# ETH.net
KiCad netlist of a schematic drawn in Altium Designer
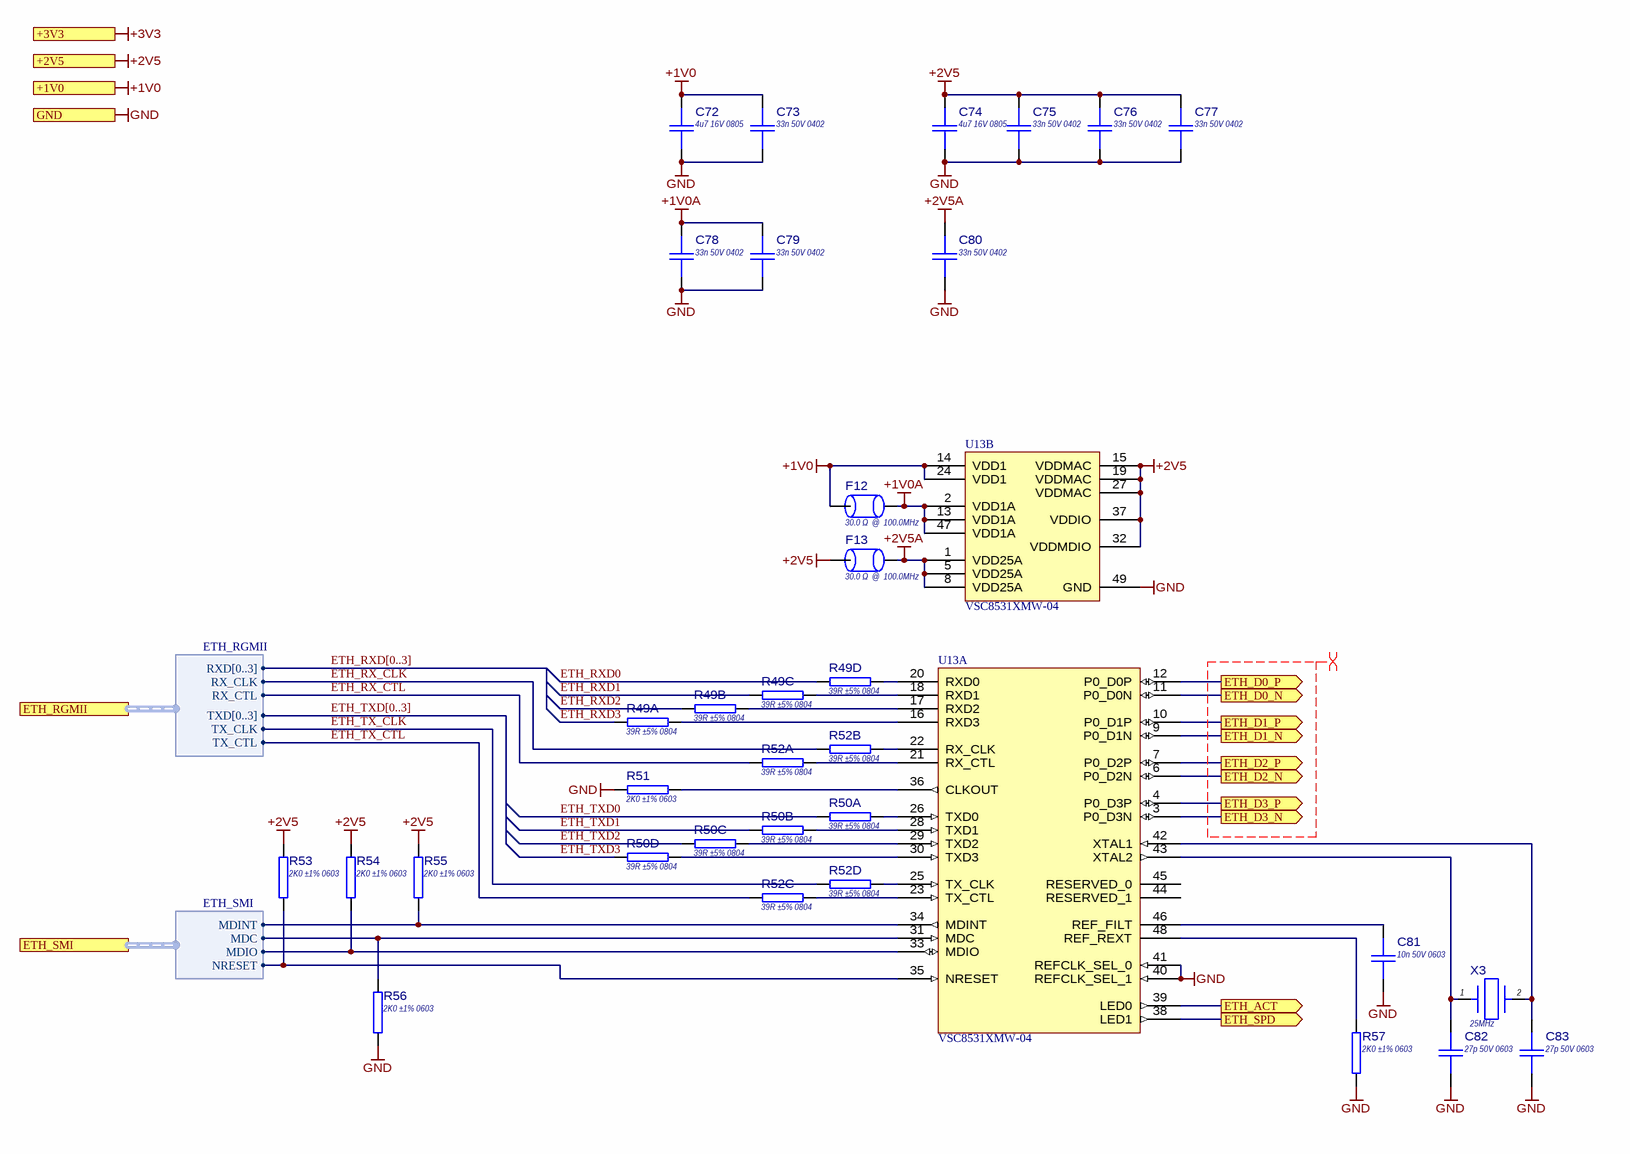
[diagram p0: ETH.SchDoc]

(export (version "E")
  (design (tool "Eeschema 10.0.6"))
  (components
    (comp (ref "C72")
      (value "4u7 16V 0805")
      (footprint "CAPC2012X140N")
      (description "4u7 16V X7R ±10% 0805 (2012 metric)")
      (fields (field (name "PARTNUMBER") "GRM21BR71C475KA73") (field (name "TOLERANCE") "10%"))
      (libsource (lib "Omnisys Vault") (part "CAP-2PIN"))
    )
    (comp (ref "C73")
      (value "33n 50V 0402")
      (footprint "CAPC1005X55N")
      (description "33n 50V X7R ±10% 0402 (1005 metric)")
      (fields (field (name "PARTNUMBER") "GRM155R71H333KE14") (field (name "TOLERANCE") "10%"))
      (libsource (lib "Omnisys Vault") (part "CAP-2PIN"))
    )
    (comp (ref "C74")
      (value "4u7 16V 0805")
      (footprint "CAPC2012X140N")
      (description "4u7 16V X7R ±10% 0805 (2012 metric)")
      (fields (field (name "PARTNUMBER") "GRM21BR71C475KA73") (field (name "TOLERANCE") "10%"))
      (libsource (lib "Omnisys Vault") (part "CAP-2PIN"))
    )
    (comp (ref "C75")
      (value "33n 50V 0402")
      (footprint "CAPC1005X55N")
      (description "33n 50V X7R ±10% 0402 (1005 metric)")
      (fields (field (name "PARTNUMBER") "GRM155R71H333KE14") (field (name "TOLERANCE") "10%"))
      (libsource (lib "Omnisys Vault") (part "CAP-2PIN"))
    )
    (comp (ref "C76")
      (value "33n 50V 0402")
      (footprint "CAPC1005X55N")
      (description "33n 50V X7R ±10% 0402 (1005 metric)")
      (fields (field (name "PARTNUMBER") "GRM155R71H333KE14") (field (name "TOLERANCE") "10%"))
      (libsource (lib "Omnisys Vault") (part "CAP-2PIN"))
    )
    (comp (ref "C77")
      (value "33n 50V 0402")
      (footprint "CAPC1005X55N")
      (description "33n 50V X7R ±10% 0402 (1005 metric)")
      (fields (field (name "PARTNUMBER") "GRM155R71H333KE14") (field (name "TOLERANCE") "10%"))
      (libsource (lib "Omnisys Vault") (part "CAP-2PIN"))
    )
    (comp (ref "C78")
      (value "33n 50V 0402")
      (footprint "CAPC1005X55N")
      (description "33n 50V X7R ±10% 0402 (1005 metric)")
      (fields (field (name "PARTNUMBER") "GRM155R71H333KE14") (field (name "TOLERANCE") "10%"))
      (libsource (lib "Omnisys Vault") (part "CAP-2PIN"))
    )
    (comp (ref "C79")
      (value "33n 50V 0402")
      (footprint "CAPC1005X55N")
      (description "33n 50V X7R ±10% 0402 (1005 metric)")
      (fields (field (name "PARTNUMBER") "GRM155R71H333KE14") (field (name "TOLERANCE") "10%"))
      (libsource (lib "Omnisys Vault") (part "CAP-2PIN"))
    )
    (comp (ref "C80")
      (value "33n 50V 0402")
      (footprint "CAPC1005X55N")
      (description "33n 50V X7R ±10% 0402 (1005 metric)")
      (fields (field (name "PARTNUMBER") "GRM155R71H333KE14") (field (name "TOLERANCE") "10%"))
      (libsource (lib "Omnisys Vault") (part "CAP-2PIN"))
    )
    (comp (ref "C81")
      (value "10n 50V 0603")
      (footprint "CAPC1608X90N")
      (description "10n 50V C0G ±5% 0603 (1608 metric)")
      (fields (field (name "PARTNUMBER") "GRM1885C1H103JA01") (field (name "TOLERANCE") "±5%"))
      (libsource (lib "Omnisys Vault") (part "CAP-2PIN"))
    )
    (comp (ref "C82")
      (value "27p 50V 0603")
      (footprint "CAPC1608X90N")
      (description "27p 50V C0G ±5% 0603 (1608 metric)")
      (fields (field (name "PARTNUMBER") "GRM1885C1H270JA01") (field (name "TOLERANCE") "±5%"))
      (libsource (lib "Omnisys Vault") (part "CAP-2PIN"))
    )
    (comp (ref "C83")
      (value "27p 50V 0603")
      (footprint "CAPC1608X90N")
      (description "27p 50V C0G ±5% 0603 (1608 metric)")
      (fields (field (name "PARTNUMBER") "GRM1885C1H270JA01") (field (name "TOLERANCE") "±5%"))
      (libsource (lib "Omnisys Vault") (part "CAP-2PIN"))
    )
    (comp (ref "F12")
      (value "30.0 Ω  @  100.0MHz")
      (footprint "INDC2012X11L")
      (description "Ferrite bead, Würth Elektronik WE-CBF 2012 (0805), 74279206 ,  30.0 Ω  @  100.0MHz")
      (fields (field (name "PARTNUMBER") "74279206"))
      (libsource (lib "Omnisys Vault") (part "BEAD-2PIN"))
    )
    (comp (ref "F13")
      (value "30.0 Ω  @  100.0MHz")
      (footprint "INDC2012X11L")
      (description "Ferrite bead, Würth Elektronik WE-CBF 2012 (0805), 74279206 ,  30.0 Ω  @  100.0MHz")
      (fields (field (name "PARTNUMBER") "74279206"))
      (libsource (lib "Omnisys Vault") (part "BEAD-2PIN"))
    )
    (comp (ref "R49")
      (value "39R ±5% 0804")
      (footprint "RESCAXS50P100X200X45-8N")
      (description "39R ±5% ±200 ppm/˚C 0.031W 50V 0804 (2010 metric)")
      (fields (field (name "TOLERANCE") "±5%") (field (name "PARTNUMBER") "EXB-28V390J"))
      (libsource (lib "Omnisys Vault") (part "RES_ARRAY-8PIN"))
    )
    (comp (ref "R50")
      (value "39R ±5% 0804")
      (footprint "RESCAXS50P100X200X45-8N")
      (description "39R ±5% ±200 ppm/˚C 0.031W 50V 0804 (2010 metric)")
      (fields (field (name "TOLERANCE") "±5%") (field (name "PARTNUMBER") "EXB-28V390J"))
      (libsource (lib "Omnisys Vault") (part "RES_ARRAY-8PIN"))
    )
    (comp (ref "R51")
      (value "2K0 ±1% 0603")
      (footprint "RESC1608N")
      (description "2K0 ±1% ±100 ppm/˚C 0.10W 75V 0603 (1608 metric)")
      (fields (field (name "POWER") "100mW") (field (name "TOLERANCE") "1%"))
      (libsource (lib "Omnisys Vault") (part "RES-2PIN"))
    )
    (comp (ref "R52")
      (value "39R ±5% 0804")
      (footprint "RESCAXS50P100X200X45-8N")
      (description "39R ±5% ±200 ppm/˚C 0.031W 50V 0804 (2010 metric)")
      (fields (field (name "TOLERANCE") "±5%") (field (name "PARTNUMBER") "EXB-28V390J"))
      (libsource (lib "Omnisys Vault") (part "RES_ARRAY-8PIN"))
    )
    (comp (ref "R53")
      (value "2K0 ±1% 0603")
      (footprint "RESC1608N")
      (description "2K0 ±1% ±100 ppm/˚C 0.10W 75V 0603 (1608 metric)")
      (fields (field (name "POWER") "100mW") (field (name "TOLERANCE") "1%"))
      (libsource (lib "Omnisys Vault") (part "RES-2PIN"))
    )
    (comp (ref "R54")
      (value "2K0 ±1% 0603")
      (footprint "RESC1608N")
      (description "2K0 ±1% ±100 ppm/˚C 0.10W 75V 0603 (1608 metric)")
      (fields (field (name "POWER") "100mW") (field (name "TOLERANCE") "1%"))
      (libsource (lib "Omnisys Vault") (part "RES-2PIN"))
    )
    (comp (ref "R55")
      (value "2K0 ±1% 0603")
      (footprint "RESC1608N")
      (description "2K0 ±1% ±100 ppm/˚C 0.10W 75V 0603 (1608 metric)")
      (fields (field (name "POWER") "100mW") (field (name "TOLERANCE") "1%"))
      (libsource (lib "Omnisys Vault") (part "RES-2PIN"))
    )
    (comp (ref "R56")
      (value "2K0 ±1% 0603")
      (footprint "RESC1608N")
      (description "2K0 ±1% ±100 ppm/˚C 0.10W 75V 0603 (1608 metric)")
      (fields (field (name "POWER") "100mW") (field (name "TOLERANCE") "1%"))
      (libsource (lib "Omnisys Vault") (part "RES-2PIN"))
    )
    (comp (ref "R57")
      (value "2K0 ±1% 0603")
      (footprint "RESC1608N")
      (description "2K0 ±1% ±100 ppm/˚C 0.10W 75V 0603 (1608 metric)")
      (fields (field (name "POWER") "100mW") (field (name "TOLERANCE") "1%"))
      (libsource (lib "Omnisys Vault") (part "RES-2PIN"))
    )
    (comp (ref "U13")
      (value "VSC8531XMW-04")
      (footprint "QFN40P600X600X90_HS-49N")
      (description "Single Port Gigabit Ethernet Copper PHY")
      (libsource (lib "Omnisys Vault") (part "VSC8531XMW-04"))
    )
    (comp (ref "X3")
      (value "25MHz")
      (footprint "XTAL_5x3.2MM")
      (description "25MHz 5 x 3.2 mm SMD GLASS CRYSTAL, 7A-25.000MAAJ-T")
      (fields (field (name "PARTNUMBER") "7A-25.000MAAJ-T"))
      (libsource (lib "Omnisys Vault") (part "XTAL-2PIN"))
    )
  )
  (nets
    (net (code "3") (name "+1V0") (class "Default")
      (node (ref "C72") (pin "2") (pinfunction "2_2") (pintype "passive"))
      (node (ref "C73") (pin "1") (pinfunction "1_1") (pintype "passive"))
      (node (ref "F12") (pin "1") (pinfunction "1_1") (pintype "passive"))
      (node (ref "U13") (pin "14") (pinfunction "VDD1_14") (pintype "power_in"))
      (node (ref "U13") (pin "24") (pinfunction "VDD1_24") (pintype "power_in"))
    )
    (net (code "4") (name "+1V0A") (class "Default")
      (node (ref "C78") (pin "1") (pinfunction "1_1") (pintype "passive"))
      (node (ref "C79") (pin "1") (pinfunction "1_1") (pintype "passive"))
      (node (ref "F12") (pin "2") (pinfunction "2_2") (pintype "passive"))
      (node (ref "U13") (pin "13") (pinfunction "VDD1A_13") (pintype "power_in"))
      (node (ref "U13") (pin "2") (pinfunction "VDD1A_2") (pintype "power_in"))
      (node (ref "U13") (pin "47") (pinfunction "VDD1A_47") (pintype "power_in"))
    )
    (net (code "5") (name "+2V5") (class "Default")
      (node (ref "C74") (pin "2") (pinfunction "2_2") (pintype "passive"))
      (node (ref "C75") (pin "1") (pinfunction "1_1") (pintype "passive"))
      (node (ref "C76") (pin "1") (pinfunction "1_1") (pintype "passive"))
      (node (ref "C77") (pin "1") (pinfunction "1_1") (pintype "passive"))
      (node (ref "F13") (pin "1") (pinfunction "1_1") (pintype "passive"))
      (node (ref "R53") (pin "2") (pinfunction "2_2") (pintype "passive"))
      (node (ref "R54") (pin "2") (pinfunction "2_2") (pintype "passive"))
      (node (ref "R55") (pin "2") (pinfunction "2_2") (pintype "passive"))
      (node (ref "U13") (pin "15") (pinfunction "VDDMAC_15") (pintype "power_in"))
      (node (ref "U13") (pin "19") (pinfunction "VDDMAC_19") (pintype "power_in"))
      (node (ref "U13") (pin "27") (pinfunction "VDDMAC_27") (pintype "power_in"))
      (node (ref "U13") (pin "32") (pinfunction "VDDMDIO_32") (pintype "power_in"))
      (node (ref "U13") (pin "37") (pinfunction "VDDIO_37") (pintype "power_in"))
    )
    (net (code "6") (name "+2V5A") (class "Default")
      (node (ref "C80") (pin "1") (pinfunction "1_1") (pintype "passive"))
      (node (ref "F13") (pin "2") (pinfunction "2_2") (pintype "passive"))
      (node (ref "U13") (pin "1") (pinfunction "VDD25A_1") (pintype "power_in"))
      (node (ref "U13") (pin "5") (pinfunction "VDD25A_5") (pintype "power_in"))
      (node (ref "U13") (pin "8") (pinfunction "VDD25A_8") (pintype "power_in"))
    )
    (net (code "8") (name "/ETH_ACT") (class "Default")
      (node (ref "U13") (pin "39") (pinfunction "LED0_39") (pintype "output"))
    )
    (net (code "9") (name "/ETH_D0_N") (class "Default")
      (node (ref "U13") (pin "11") (pinfunction "P0_D0N_11") (pintype "bidirectional"))
    )
    (net (code "10") (name "/ETH_D0_P") (class "Default")
      (node (ref "U13") (pin "12") (pinfunction "P0_D0P_12") (pintype "bidirectional"))
    )
    (net (code "11") (name "/ETH_D1_N") (class "Default")
      (node (ref "U13") (pin "9") (pinfunction "P0_D1N_9") (pintype "bidirectional"))
    )
    (net (code "12") (name "/ETH_D1_P") (class "Default")
      (node (ref "U13") (pin "10") (pinfunction "P0_D1P_10") (pintype "bidirectional"))
    )
    (net (code "13") (name "/ETH_D2_N") (class "Default")
      (node (ref "U13") (pin "6") (pinfunction "P0_D2N_6") (pintype "bidirectional"))
    )
    (net (code "14") (name "/ETH_D2_P") (class "Default")
      (node (ref "U13") (pin "7") (pinfunction "P0_D2P_7") (pintype "bidirectional"))
    )
    (net (code "15") (name "/ETH_D3_N") (class "Default")
      (node (ref "U13") (pin "3") (pinfunction "P0_D3N_3") (pintype "bidirectional"))
    )
    (net (code "16") (name "/ETH_D3_P") (class "Default")
      (node (ref "U13") (pin "4") (pinfunction "P0_D3P_4") (pintype "bidirectional"))
    )
    (net (code "17") (name "/ETH_RXD0") (class "Default") (node (ref "R49") (pin "4") (pintype "passive")))
    (net (code "18") (name "/ETH_RXD1") (class "Default") (node (ref "R49") (pin "3") (pintype "passive")))
    (net (code "19") (name "/ETH_RXD2") (class "Default") (node (ref "R49") (pin "2") (pintype "passive")))
    (net (code "20") (name "/ETH_RXD3") (class "Default") (node (ref "R49") (pin "1") (pintype "passive")))
    (net (code "22") (name "/ETH_RX_CLK") (class "Default") (node (ref "R52") (pin "2") (pintype "passive")))
    (net (code "23") (name "/ETH_RX_CTL") (class "Default") (node (ref "R52") (pin "1") (pintype "passive")))
    (net (code "24") (name "/ETH_SPD") (class "Default")
      (node (ref "U13") (pin "38") (pinfunction "LED1_38") (pintype "output"))
    )
    (net (code "25") (name "/ETH_TXD0") (class "Default") (node (ref "R50") (pin "1") (pintype "passive")))
    (net (code "26") (name "/ETH_TXD1") (class "Default") (node (ref "R50") (pin "2") (pintype "passive")))
    (net (code "27") (name "/ETH_TXD2") (class "Default") (node (ref "R50") (pin "3") (pintype "passive")))
    (net (code "28") (name "/ETH_TXD3") (class "Default") (node (ref "R50") (pin "4") (pintype "passive")))
    (net (code "30") (name "/ETH_TX_CLK") (class "Default") (node (ref "R52") (pin "4") (pintype "passive")))
    (net (code "31") (name "/ETH_TX_CTL") (class "Default") (node (ref "R52") (pin "3") (pintype "passive")))
    (net (code "34") (name "GND") (class "Default")
      (node (ref "C72") (pin "1") (pinfunction "1_1") (pintype "passive"))
      (node (ref "C73") (pin "2") (pinfunction "2_2") (pintype "passive"))
      (node (ref "C74") (pin "1") (pinfunction "1_1") (pintype "passive"))
      (node (ref "C75") (pin "2") (pinfunction "2_2") (pintype "passive"))
      (node (ref "C76") (pin "2") (pinfunction "2_2") (pintype "passive"))
      (node (ref "C77") (pin "2") (pinfunction "2_2") (pintype "passive"))
      (node (ref "C78") (pin "2") (pinfunction "2_2") (pintype "passive"))
      (node (ref "C79") (pin "2") (pinfunction "2_2") (pintype "passive"))
      (node (ref "C80") (pin "2") (pinfunction "2_2") (pintype "passive"))
      (node (ref "C81") (pin "2") (pinfunction "2_2") (pintype "passive"))
      (node (ref "C82") (pin "1") (pinfunction "1_1") (pintype "passive"))
      (node (ref "C83") (pin "1") (pinfunction "1_1") (pintype "passive"))
      (node (ref "R51") (pin "2") (pinfunction "2_2") (pintype "passive"))
      (node (ref "R56") (pin "1") (pinfunction "1_1") (pintype "passive"))
      (node (ref "R57") (pin "1") (pinfunction "1_1") (pintype "passive"))
      (node (ref "U13") (pin "40") (pinfunction "REFCLK_SEL_1_40") (pintype "input"))
      (node (ref "U13") (pin "41") (pinfunction "REFCLK_SEL_0_41") (pintype "input"))
      (node (ref "U13") (pin "49") (pinfunction "GND_49") (pintype "power_in"))
    )
    (net (code "35") (name "Net-(U13A-CLKOUT)") (class "Default")
      (node (ref "R51") (pin "1") (pinfunction "1_1") (pintype "passive"))
      (node (ref "U13") (pin "36") (pinfunction "CLKOUT_36") (pintype "output"))
    )
    (net (code "36") (name "Net-(U13A-MDC)") (class "Default")
      (node (ref "R56") (pin "2") (pinfunction "2_2") (pintype "passive"))
      (node (ref "U13") (pin "31") (pinfunction "MDC_31") (pintype "input"))
    )
    (net (code "37") (name "Net-(U13A-MDINT)") (class "Default")
      (node (ref "R55") (pin "1") (pinfunction "1_1") (pintype "passive"))
      (node (ref "U13") (pin "34") (pinfunction "MDINT_34") (pintype "output"))
    )
    (net (code "38") (name "Net-(U13A-MDIO)") (class "Default")
      (node (ref "R54") (pin "1") (pinfunction "1_1") (pintype "passive"))
      (node (ref "U13") (pin "33") (pinfunction "MDIO_33") (pintype "bidirectional"))
    )
    (net (code "39") (name "Net-(U13A-NRESET)") (class "Default")
      (node (ref "R53") (pin "1") (pinfunction "1_1") (pintype "passive"))
      (node (ref "U13") (pin "35") (pinfunction "NRESET_35") (pintype "input"))
    )
    (net (code "40") (name "Net-(U13A-REF_FILT)") (class "Default")
      (node (ref "C81") (pin "1") (pinfunction "1_1") (pintype "passive"))
      (node (ref "U13") (pin "46") (pinfunction "REF_FILT_46") (pintype "power_in"))
    )
    (net (code "41") (name "Net-(U13A-REF_REXT)") (class "Default")
      (node (ref "R57") (pin "2") (pinfunction "2_2") (pintype "passive"))
      (node (ref "U13") (pin "48") (pinfunction "REF_REXT_48") (pintype "power_in"))
    )
    (net (code "42") (name "Net-(U13A-RXD0)") (class "Default")
      (node (ref "R49") (pin "5") (pintype "passive"))
      (node (ref "U13") (pin "20") (pinfunction "RXD0_20") (pintype "passive"))
    )
    (net (code "43") (name "Net-(U13A-RXD1)") (class "Default")
      (node (ref "R49") (pin "6") (pintype "passive"))
      (node (ref "U13") (pin "18") (pinfunction "RXD1_18") (pintype "passive"))
    )
    (net (code "44") (name "Net-(U13A-RXD2)") (class "Default")
      (node (ref "R49") (pin "7") (pintype "passive"))
      (node (ref "U13") (pin "17") (pinfunction "RXD2_17") (pintype "passive"))
    )
    (net (code "45") (name "Net-(U13A-RXD3)") (class "Default")
      (node (ref "R49") (pin "8") (pintype "passive"))
      (node (ref "U13") (pin "16") (pinfunction "RXD3_16") (pintype "passive"))
    )
    (net (code "46") (name "Net-(U13A-RX_CLK)") (class "Default")
      (node (ref "R52") (pin "7") (pintype "passive"))
      (node (ref "U13") (pin "22") (pinfunction "RX_CLK_22") (pintype "passive"))
    )
    (net (code "47") (name "Net-(U13A-RX_CTL)") (class "Default")
      (node (ref "R52") (pin "8") (pintype "passive"))
      (node (ref "U13") (pin "21") (pinfunction "RX_CTL_21") (pintype "passive"))
    )
    (net (code "48") (name "Net-(U13A-TXD0)") (class "Default")
      (node (ref "R50") (pin "8") (pintype "passive"))
      (node (ref "U13") (pin "26") (pinfunction "TXD0_26") (pintype "input"))
    )
    (net (code "49") (name "Net-(U13A-TXD1)") (class "Default")
      (node (ref "R50") (pin "7") (pintype "passive"))
      (node (ref "U13") (pin "28") (pinfunction "TXD1_28") (pintype "input"))
    )
    (net (code "50") (name "Net-(U13A-TXD2)") (class "Default")
      (node (ref "R50") (pin "6") (pintype "passive"))
      (node (ref "U13") (pin "29") (pinfunction "TXD2_29") (pintype "input"))
    )
    (net (code "51") (name "Net-(U13A-TXD3)") (class "Default")
      (node (ref "R50") (pin "5") (pintype "passive"))
      (node (ref "U13") (pin "30") (pinfunction "TXD3_30") (pintype "input"))
    )
    (net (code "52") (name "Net-(U13A-TX_CLK)") (class "Default")
      (node (ref "R52") (pin "5") (pintype "passive"))
      (node (ref "U13") (pin "25") (pinfunction "TX_CLK_25") (pintype "input"))
    )
    (net (code "53") (name "Net-(U13A-TX_CTL)") (class "Default")
      (node (ref "R52") (pin "6") (pintype "passive"))
      (node (ref "U13") (pin "23") (pinfunction "TX_CTL_23") (pintype "input"))
    )
    (net (code "54") (name "Net-(U13A-XTAL1)") (class "Default")
      (node (ref "C83") (pin "2") (pinfunction "2_2") (pintype "passive"))
      (node (ref "U13") (pin "42") (pinfunction "XTAL1_42") (pintype "input"))
      (node (ref "X3") (pin "2") (pinfunction "2_2") (pintype "passive"))
    )
    (net (code "55") (name "Net-(U13A-XTAL2)") (class "Default")
      (node (ref "C82") (pin "2") (pinfunction "2_2") (pintype "passive"))
      (node (ref "U13") (pin "43") (pinfunction "XTAL2_43") (pintype "output"))
      (node (ref "X3") (pin "1") (pinfunction "1_1") (pintype "passive"))
    )
    (net (code "56") (name "unconnected-(U13A-RESERVED_0-Pad45)") (class "Default")
      (node (ref "U13") (pin "45") (pinfunction "RESERVED_0_45") (pintype "passive"))
    )
    (net (code "57") (name "unconnected-(U13A-RESERVED_1-Pad44)") (class "Default")
      (node (ref "U13") (pin "44") (pinfunction "RESERVED_1_44") (pintype "passive"))
    )
  )
)
